# Sheet1.net
KiCad netlist of a schematic drawn in Altium Designer
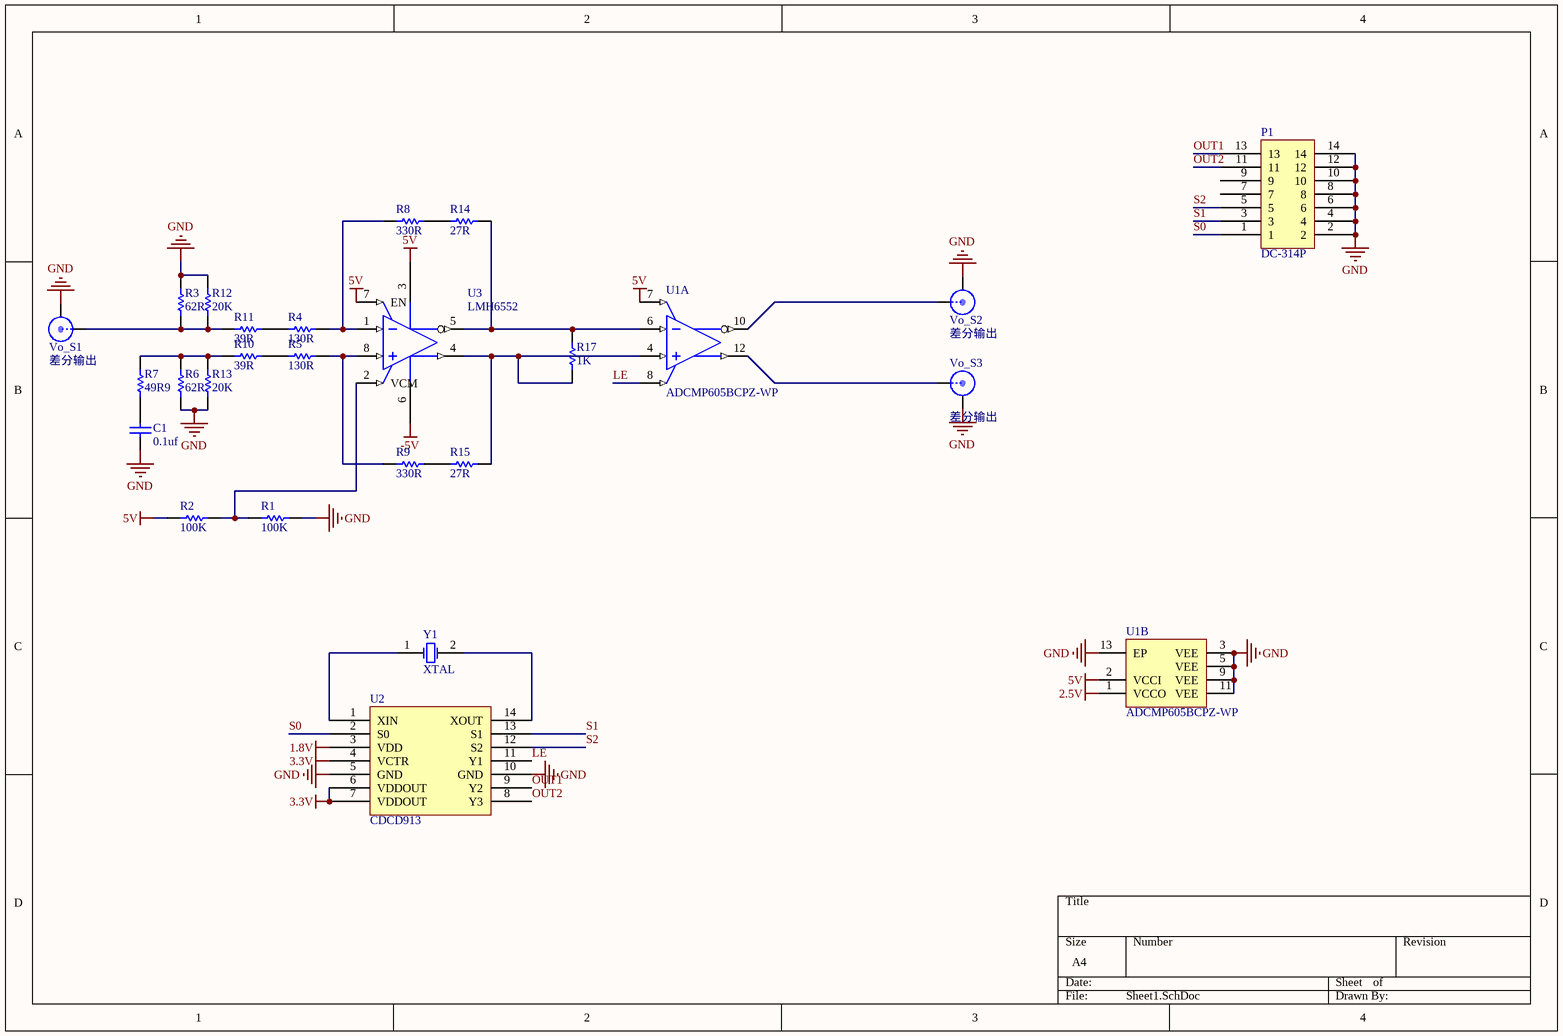
[diagram p0: Sheet1.SchDoc]

(export (version "E")
  (design (tool "Eeschema 10.0.6"))
  (components
    (comp (ref "C1") (value "0.1uf") (footprint "0805") (libsource (lib "Schlib1") (part "Cap")))
    (comp (ref "P1") (value "DC-314P") (footprint "DC3-14P") (libsource (lib "Schlib1") (part "DC3-14P")))
    (comp (ref "R1") (value "100K") (footprint "0805") (libsource (lib "Schlib1") (part "Res")))
    (comp (ref "R2") (value "100K") (footprint "0805") (libsource (lib "Schlib1") (part "Res")))
    (comp (ref "R3") (value "62R") (footprint "0805") (libsource (lib "Schlib1") (part "Res")))
    (comp (ref "R4") (value "130R") (footprint "0805") (libsource (lib "Schlib1") (part "Res")))
    (comp (ref "R5") (value "130R") (footprint "0805") (libsource (lib "Schlib1") (part "Res")))
    (comp (ref "R6") (value "62R") (footprint "0805") (libsource (lib "Schlib1") (part "Res")))
    (comp (ref "R7") (value "49R9") (footprint "0805") (libsource (lib "Schlib1") (part "Res")))
    (comp (ref "R8") (value "330R") (footprint "0805") (libsource (lib "Schlib1") (part "Res")))
    (comp (ref "R9") (value "330R") (footprint "0805") (libsource (lib "Schlib1") (part "Res")))
    (comp (ref "R10") (value "39R") (footprint "0805") (libsource (lib "Schlib1") (part "Res")))
    (comp (ref "R11") (value "39R") (footprint "0805") (libsource (lib "Schlib1") (part "Res")))
    (comp (ref "R12") (value "20K") (footprint "0805") (libsource (lib "Schlib1") (part "Res")))
    (comp (ref "R13") (value "20K") (footprint "0805") (libsource (lib "Schlib1") (part "Res")))
    (comp (ref "R14") (value "27R") (footprint "0805") (libsource (lib "Schlib1") (part "Res")))
    (comp (ref "R15") (value "27R") (footprint "0805") (libsource (lib "Schlib1") (part "Res")))
    (comp (ref "R17") (value "1K") (footprint "0805") (libsource (lib "Schlib1") (part "Res")))
    (comp (ref "U1")
      (value "ADCMP605BCPZ-WP")
      (footprint "ADI-CP-12-1_N")
      (fields (field (name "MANUFACTURER") "Analog Devices"))
      (libsource (lib "Schlib1") (part "ADCMP605BCPZ-WP"))
    )
    (comp (ref "U2") (value "CDCD913") (footprint "RU-14_L") (libsource (lib "Schlib1") (part "CDCD913")))
    (comp (ref "U3") (value "LMH6552") (footprint "TI-D8_L") (libsource (lib "Schlib1") (part "LMH6552")))
    (comp (ref "Vo_S1") (value "差分输出") (footprint "SMA-LYING") (libsource (lib "Schlib1") (part "SMA")))
    (comp (ref "Vo_S2") (value "差分输出") (footprint "SMA-LYING") (libsource (lib "Schlib1") (part "SMA")))
    (comp (ref "Vo_S3") (value "差分输出") (footprint "SMA-LYING") (libsource (lib "Schlib1") (part "SMA")))
    (comp (ref "Y1")
      (value "XTAL")
      (footprint "HC-49S")
      (description "Crystal Oscillator")
      (fields (field (name "PUBLISHER") "Altium Limited"))
      (libsource (lib "Miscellaneous Devices") (part "XTAL"))
    )
  )
  (nets
    (net (code "1") (name "-5V") (class "Default")
      (node (ref "U3") (pin "6") (pinfunction "VDD_6") (pintype "passive"))
    )
    (net (code "2") (name "/LE") (class "Default")
      (node (ref "U1") (pin "8") (pinfunction "LE/HYS_8") (pintype "input"))
      (node (ref "U2") (pin "11") (pinfunction "Y1_11") (pintype "passive"))
    )
    (net (code "3") (name "/OUT1") (class "Default")
      (node (ref "P1") (pin "13") (pinfunction "13_13") (pintype "passive"))
      (node (ref "U2") (pin "9") (pinfunction "Y2_9") (pintype "passive"))
    )
    (net (code "4") (name "/OUT2") (class "Default")
      (node (ref "P1") (pin "11") (pinfunction "11_11") (pintype "passive"))
      (node (ref "U2") (pin "8") (pinfunction "Y3_8") (pintype "passive"))
    )
    (net (code "5") (name "/S0") (class "Default")
      (node (ref "P1") (pin "1") (pinfunction "1_1") (pintype "passive"))
      (node (ref "U2") (pin "2") (pinfunction "S0_2") (pintype "passive"))
    )
    (net (code "6") (name "/S1") (class "Default")
      (node (ref "P1") (pin "3") (pinfunction "3_3") (pintype "passive"))
      (node (ref "U2") (pin "13") (pinfunction "S1_13") (pintype "passive"))
    )
    (net (code "7") (name "/S2") (class "Default")
      (node (ref "P1") (pin "5") (pinfunction "5_5") (pintype "passive"))
      (node (ref "U2") (pin "12") (pinfunction "S2_12") (pintype "passive"))
    )
    (net (code "8") (name "1.8V") (class "Default")
      (node (ref "U2") (pin "3") (pinfunction "VDD_3") (pintype "passive"))
    )
    (net (code "9") (name "2.5V") (class "Default")
      (node (ref "U1") (pin "1") (pinfunction "VCCO_1") (pintype "power_in"))
    )
    (net (code "10") (name "3.3V") (class "Default")
      (node (ref "U2") (pin "4") (pinfunction "VCTR_4") (pintype "passive"))
      (node (ref "U2") (pin "6") (pinfunction "VDDOUT_6") (pintype "passive"))
      (node (ref "U2") (pin "7") (pinfunction "VDDOUT_7") (pintype "passive"))
    )
    (net (code "11") (name "5V") (class "Default")
      (node (ref "R2") (pin "1") (pinfunction "1_1") (pintype "passive"))
      (node (ref "U1") (pin "2") (pinfunction "VCCI_2") (pintype "power_in"))
      (node (ref "U1") (pin "7") (pinfunction "SDN_7") (pintype "input"))
      (node (ref "U3") (pin "3") (pinfunction "VCC_3") (pintype "passive"))
      (node (ref "U3") (pin "7") (pinfunction "EN_7") (pintype "input"))
    )
    (net (code "12") (name "GND") (class "Default")
      (node (ref "C1") (pin "1") (pinfunction "1_1") (pintype "passive"))
      (node (ref "P1") (pin "10") (pinfunction "10_10") (pintype "passive"))
      (node (ref "P1") (pin "12") (pinfunction "12_12") (pintype "passive"))
      (node (ref "P1") (pin "14") (pinfunction "14_14") (pintype "passive"))
      (node (ref "P1") (pin "2") (pinfunction "2_2") (pintype "passive"))
      (node (ref "P1") (pin "4") (pinfunction "4_4") (pintype "passive"))
      (node (ref "P1") (pin "6") (pinfunction "6_6") (pintype "passive"))
      (node (ref "P1") (pin "8") (pinfunction "8_8") (pintype "passive"))
      (node (ref "R1") (pin "2") (pinfunction "2_2") (pintype "passive"))
      (node (ref "R12") (pin "2") (pinfunction "2_2") (pintype "passive"))
      (node (ref "R13") (pin "1") (pinfunction "1_1") (pintype "passive"))
      (node (ref "R3") (pin "2") (pinfunction "2_2") (pintype "passive"))
      (node (ref "R6") (pin "2") (pinfunction "2_2") (pintype "passive"))
      (node (ref "U1") (pin "11") (pinfunction "VEE_11") (pintype "power_in"))
      (node (ref "U1") (pin "13") (pinfunction "EP_13") (pintype "passive"))
      (node (ref "U1") (pin "3") (pinfunction "VEE_3") (pintype "power_in"))
      (node (ref "U1") (pin "5") (pinfunction "VEE_5") (pintype "power_in"))
      (node (ref "U1") (pin "9") (pinfunction "VEE_9") (pintype "power_in"))
      (node (ref "U2") (pin "10") (pinfunction "GND_10") (pintype "passive"))
      (node (ref "U2") (pin "5") (pinfunction "GND_5") (pintype "passive"))
      (node (ref "Vo_S1") (pin "1") (pinfunction "1_1") (pintype "passive"))
      (node (ref "Vo_S2") (pin "1") (pinfunction "1_1") (pintype "passive"))
      (node (ref "Vo_S3") (pin "1") (pinfunction "1_1") (pintype "passive"))
    )
    (net (code "13") (name "Net-(C1-Pad2)") (class "Default")
      (node (ref "C1") (pin "2") (pinfunction "2_2") (pintype "passive"))
      (node (ref "R7") (pin "2") (pinfunction "2_2") (pintype "passive"))
    )
    (net (code "14") (name "Net-(R10-Pad1)") (class "Default")
      (node (ref "R10") (pin "1") (pinfunction "1_1") (pintype "passive"))
      (node (ref "R13") (pin "2") (pinfunction "2_2") (pintype "passive"))
      (node (ref "R6") (pin "1") (pinfunction "1_1") (pintype "passive"))
      (node (ref "R7") (pin "1") (pinfunction "1_1") (pintype "passive"))
    )
    (net (code "15") (name "Net-(R10-Pad2)") (class "Default")
      (node (ref "R10") (pin "2") (pinfunction "2_2") (pintype "passive"))
      (node (ref "R5") (pin "2") (pinfunction "2_2") (pintype "passive"))
    )
    (net (code "16") (name "Net-(R11-Pad1)") (class "Default")
      (node (ref "R11") (pin "1") (pinfunction "1_1") (pintype "passive"))
      (node (ref "R12") (pin "1") (pinfunction "1_1") (pintype "passive"))
      (node (ref "R3") (pin "1") (pinfunction "1_1") (pintype "passive"))
      (node (ref "Vo_S1") (pin "0") (pinfunction "0_0") (pintype "passive"))
    )
    (net (code "17") (name "Net-(R11-Pad2)") (class "Default")
      (node (ref "R11") (pin "2") (pinfunction "2_2") (pintype "passive"))
      (node (ref "R4") (pin "2") (pinfunction "2_2") (pintype "passive"))
    )
    (net (code "18") (name "Net-(R14-Pad2)") (class "Default")
      (node (ref "R14") (pin "2") (pinfunction "2_2") (pintype "passive"))
      (node (ref "R8") (pin "2") (pinfunction "2_2") (pintype "passive"))
    )
    (net (code "19") (name "Net-(R15-Pad2)") (class "Default")
      (node (ref "R15") (pin "2") (pinfunction "2_2") (pintype "passive"))
      (node (ref "R9") (pin "2") (pinfunction "2_2") (pintype "passive"))
    )
    (net (code "20") (name "Net-(U1A-Q)") (class "Default")
      (node (ref "U1") (pin "12") (pinfunction "Q_12") (pintype "output"))
      (node (ref "Vo_S3") (pin "0") (pinfunction "0_0") (pintype "passive"))
    )
    (net (code "21") (name "Net-(U1A-VN)") (class "Default")
      (node (ref "R14") (pin "1") (pinfunction "1_1") (pintype "passive"))
      (node (ref "R17") (pin "2") (pinfunction "2_2") (pintype "passive"))
      (node (ref "U1") (pin "6") (pinfunction "VN_6") (pintype "input"))
      (node (ref "U3") (pin "5") (pinfunction "~{Q}_5") (pintype "output"))
    )
    (net (code "22") (name "Net-(U1A-VP)") (class "Default")
      (node (ref "R15") (pin "1") (pinfunction "1_1") (pintype "passive"))
      (node (ref "R17") (pin "1") (pinfunction "1_1") (pintype "passive"))
      (node (ref "U1") (pin "4") (pinfunction "VP_4") (pintype "input"))
      (node (ref "U3") (pin "4") (pinfunction "Q_4") (pintype "output"))
    )
    (net (code "23") (name "Net-(U1A-~{Q})") (class "Default")
      (node (ref "U1") (pin "10") (pinfunction "~{Q}_10") (pintype "output"))
      (node (ref "Vo_S2") (pin "0") (pinfunction "0_0") (pintype "passive"))
    )
    (net (code "24") (name "Net-(U2-XIN)") (class "Default")
      (node (ref "U2") (pin "1") (pinfunction "XIN_1") (pintype "passive"))
      (node (ref "Y1") (pin "1") (pinfunction "OSC1_1") (pintype "passive"))
    )
    (net (code "25") (name "Net-(U2-XOUT)") (class "Default")
      (node (ref "U2") (pin "14") (pinfunction "XOUT_14") (pintype "passive"))
      (node (ref "Y1") (pin "2") (pinfunction "OSC2_2") (pintype "passive"))
    )
    (net (code "26") (name "Net-(U3-VCM)") (class "Default")
      (node (ref "R1") (pin "1") (pinfunction "1_1") (pintype "passive"))
      (node (ref "R2") (pin "2") (pinfunction "2_2") (pintype "passive"))
      (node (ref "U3") (pin "2") (pinfunction "VCM_2") (pintype "input"))
    )
    (net (code "27") (name "Net-(U3-VN)") (class "Default")
      (node (ref "R4") (pin "1") (pinfunction "1_1") (pintype "passive"))
      (node (ref "R8") (pin "1") (pinfunction "1_1") (pintype "passive"))
      (node (ref "U3") (pin "1") (pinfunction "VN_1") (pintype "input"))
    )
    (net (code "28") (name "Net-(U3-VP)") (class "Default")
      (node (ref "R5") (pin "1") (pinfunction "1_1") (pintype "passive"))
      (node (ref "R9") (pin "1") (pinfunction "1_1") (pintype "passive"))
      (node (ref "U3") (pin "8") (pinfunction "VP_8") (pintype "input"))
    )
    (net (code "29") (name "unconnected-(P1-Pad7)") (class "Default")
      (node (ref "P1") (pin "7") (pinfunction "7_7") (pintype "passive"))
    )
    (net (code "30") (name "unconnected-(P1-Pad9)") (class "Default")
      (node (ref "P1") (pin "9") (pinfunction "9_9") (pintype "passive"))
    )
  )
)
